# Sheet6.net
KiCad netlist of a schematic drawn in Altium Designer
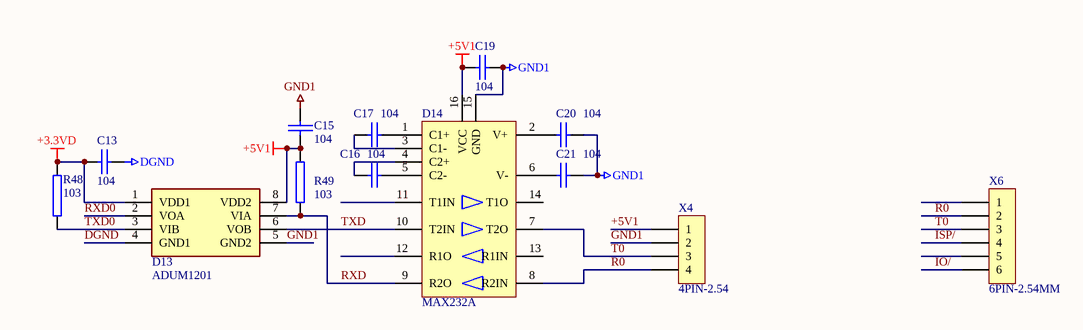
[diagram p0: Sheet6.SchDoc]

(export (version "E")
  (design (tool "Eeschema 10.0.6"))
  (components
    (comp (ref "C13")
      (value "104")
      (footprint "0603X")
      (description "Capacitor")
      (libsource (lib "*") (part "CAP"))
    )
    (comp (ref "C15")
      (value "104")
      (footprint "0603X")
      (description "Capacitor")
      (libsource (lib "*") (part "CAP"))
    )
    (comp (ref "C16")
      (value "104")
      (footprint "0603X")
      (description "Capacitor")
      (libsource (lib "*") (part "CAP"))
    )
    (comp (ref "C17")
      (value "104")
      (footprint "0603X")
      (description "Capacitor")
      (libsource (lib "*") (part "CAP"))
    )
    (comp (ref "C19")
      (value "104")
      (footprint "0603X")
      (description "Capacitor")
      (libsource (lib "*") (part "CAP"))
    )
    (comp (ref "C20")
      (value "104")
      (footprint "0603X")
      (description "Capacitor")
      (libsource (lib "*") (part "CAP"))
    )
    (comp (ref "C21")
      (value "104")
      (footprint "0603X")
      (description "Capacitor")
      (libsource (lib "*") (part "CAP"))
    )
    (comp (ref "D13") (value "ADUM1201") (footprint "SMD8XX") (libsource (lib "*") (part "ADUM1201")))
    (comp (ref "D14") (value "MAX232A") (footprint "SMD16XX") (libsource (lib "*") (part "MAX232A")))
    (comp (ref "R48") (value "103") (footprint "0603X") (libsource (lib "*") (part "RES2")))
    (comp (ref "R49") (value "103") (footprint "0603X") (libsource (lib "*") (part "RES2")))
    (comp (ref "X4")
      (value "4PIN-2.54")
      (footprint "SIP4X")
      (description "Connector")
      (libsource (lib "*") (part "CON4"))
    )
    (comp (ref "X6")
      (value "6PIN-2.54MM")
      (footprint "SIP6X")
      (description "Connector")
      (libsource (lib "*") (part "CON6"))
    )
  )
  (nets
    (net (code "1") (name "+3.3VD") (class "Default")
      (node (ref "C13") (pin "1") (pinfunction "1_1") (pintype "passive"))
      (node (ref "D13") (pin "1") (pinfunction "VDD1_1") (pintype "passive"))
      (node (ref "R48") (pin "2") (pintype "passive"))
    )
    (net (code "2") (name "+5V1") (class "Default")
      (node (ref "C15") (pin "1") (pinfunction "1_1") (pintype "passive"))
      (node (ref "C19") (pin "2") (pinfunction "2_2") (pintype "passive"))
      (node (ref "D13") (pin "8") (pinfunction "VDD2_8") (pintype "passive"))
      (node (ref "D14") (pin "16") (pinfunction "VCC_16") (pintype "passive"))
      (node (ref "R49") (pin "2") (pintype "passive"))
      (node (ref "X4") (pin "1") (pinfunction "1_1") (pintype "passive"))
    )
    (net (code "3") (name "/IO{slash}") (class "Default")
      (node (ref "X6") (pin "6") (pinfunction "6_6") (pintype "passive"))
    )
    (net (code "4") (name "/ISP{slash}") (class "Default")
      (node (ref "X6") (pin "4") (pinfunction "4_4") (pintype "passive"))
    )
    (net (code "5") (name "/R0") (class "Default")
      (node (ref "D14") (pin "8") (pinfunction "R2IN_8") (pintype "passive"))
      (node (ref "X4") (pin "4") (pinfunction "4_4") (pintype "passive"))
      (node (ref "X6") (pin "2") (pinfunction "2_2") (pintype "passive"))
    )
    (net (code "6") (name "/RXD") (class "Default")
      (node (ref "D13") (pin "7") (pinfunction "VIA_7") (pintype "passive"))
      (node (ref "D14") (pin "9") (pinfunction "R2O_9") (pintype "passive"))
      (node (ref "R49") (pin "1") (pintype "passive"))
    )
    (net (code "7") (name "/RXD0") (class "Default")
      (node (ref "D13") (pin "2") (pinfunction "VOA_2") (pintype "passive"))
    )
    (net (code "8") (name "/T0") (class "Default")
      (node (ref "D14") (pin "7") (pinfunction "T2O_7") (pintype "passive"))
      (node (ref "X4") (pin "3") (pinfunction "3_3") (pintype "passive"))
      (node (ref "X6") (pin "3") (pinfunction "3_3") (pintype "passive"))
    )
    (net (code "9") (name "/TXD") (class "Default")
      (node (ref "D13") (pin "6") (pinfunction "VOB_6") (pintype "passive"))
      (node (ref "D14") (pin "10") (pinfunction "T2IN_10") (pintype "passive"))
    )
    (net (code "10") (name "/TXD0") (class "Default")
      (node (ref "D13") (pin "3") (pinfunction "VIB_3") (pintype "passive"))
      (node (ref "R48") (pin "1") (pintype "passive"))
    )
    (net (code "11") (name "DGND") (class "Default")
      (node (ref "C13") (pin "2") (pinfunction "2_2") (pintype "passive"))
      (node (ref "D13") (pin "4") (pinfunction "GND1_4") (pintype "passive"))
    )
    (net (code "12") (name "GND1") (class "Default")
      (node (ref "C15") (pin "2") (pinfunction "2_2") (pintype "passive"))
      (node (ref "C19") (pin "1") (pinfunction "1_1") (pintype "passive"))
      (node (ref "C20") (pin "1") (pinfunction "1_1") (pintype "passive"))
      (node (ref "C21") (pin "1") (pinfunction "1_1") (pintype "passive"))
      (node (ref "D13") (pin "5") (pinfunction "GND2_5") (pintype "passive"))
      (node (ref "D14") (pin "15") (pinfunction "GND_15") (pintype "passive"))
      (node (ref "X4") (pin "2") (pinfunction "2_2") (pintype "passive"))
    )
    (net (code "13") (name "Net-(D14-C1+)") (class "Default")
      (node (ref "C17") (pin "1") (pinfunction "1_1") (pintype "passive"))
      (node (ref "D14") (pin "1") (pinfunction "C1+_1") (pintype "passive"))
    )
    (net (code "14") (name "Net-(D14-C1-)") (class "Default")
      (node (ref "C17") (pin "2") (pinfunction "2_2") (pintype "passive"))
      (node (ref "D14") (pin "3") (pinfunction "C1-_3") (pintype "passive"))
    )
    (net (code "15") (name "Net-(D14-C2+)") (class "Default")
      (node (ref "C16") (pin "2") (pinfunction "2_2") (pintype "passive"))
      (node (ref "D14") (pin "4") (pinfunction "C2+_4") (pintype "passive"))
    )
    (net (code "16") (name "Net-(D14-C2-)") (class "Default")
      (node (ref "C16") (pin "1") (pinfunction "1_1") (pintype "passive"))
      (node (ref "D14") (pin "5") (pinfunction "C2-_5") (pintype "passive"))
    )
    (net (code "17") (name "Net-(D14-V+)") (class "Default")
      (node (ref "C20") (pin "2") (pinfunction "2_2") (pintype "passive"))
      (node (ref "D14") (pin "2") (pinfunction "V+_2") (pintype "passive"))
    )
    (net (code "18") (name "Net-(D14-V-)") (class "Default")
      (node (ref "C21") (pin "2") (pinfunction "2_2") (pintype "passive"))
      (node (ref "D14") (pin "6") (pinfunction "V-_6") (pintype "passive"))
    )
    (net (code "19") (name "unconnected-(D14-R1IN-Pad13)") (class "Default")
      (node (ref "D14") (pin "13") (pinfunction "R1IN_13") (pintype "passive"))
    )
    (net (code "20") (name "unconnected-(D14-R1O-Pad12)") (class "Default")
      (node (ref "D14") (pin "12") (pinfunction "R1O_12") (pintype "passive"))
    )
    (net (code "21") (name "unconnected-(D14-T1IN-Pad11)") (class "Default")
      (node (ref "D14") (pin "11") (pinfunction "T1IN_11") (pintype "passive"))
    )
    (net (code "22") (name "unconnected-(D14-T1O-Pad14)") (class "Default")
      (node (ref "D14") (pin "14") (pinfunction "T1O_14") (pintype "passive"))
    )
    (net (code "23") (name "unconnected-(X6-Pad1)") (class "Default")
      (node (ref "X6") (pin "1") (pinfunction "1_1") (pintype "passive"))
    )
    (net (code "24") (name "unconnected-(X6-Pad5)") (class "Default")
      (node (ref "X6") (pin "5") (pinfunction "5_5") (pintype "passive"))
    )
  )
)
